# Top_PCB.net
KiCad netlist of a schematic drawn in EAGLE
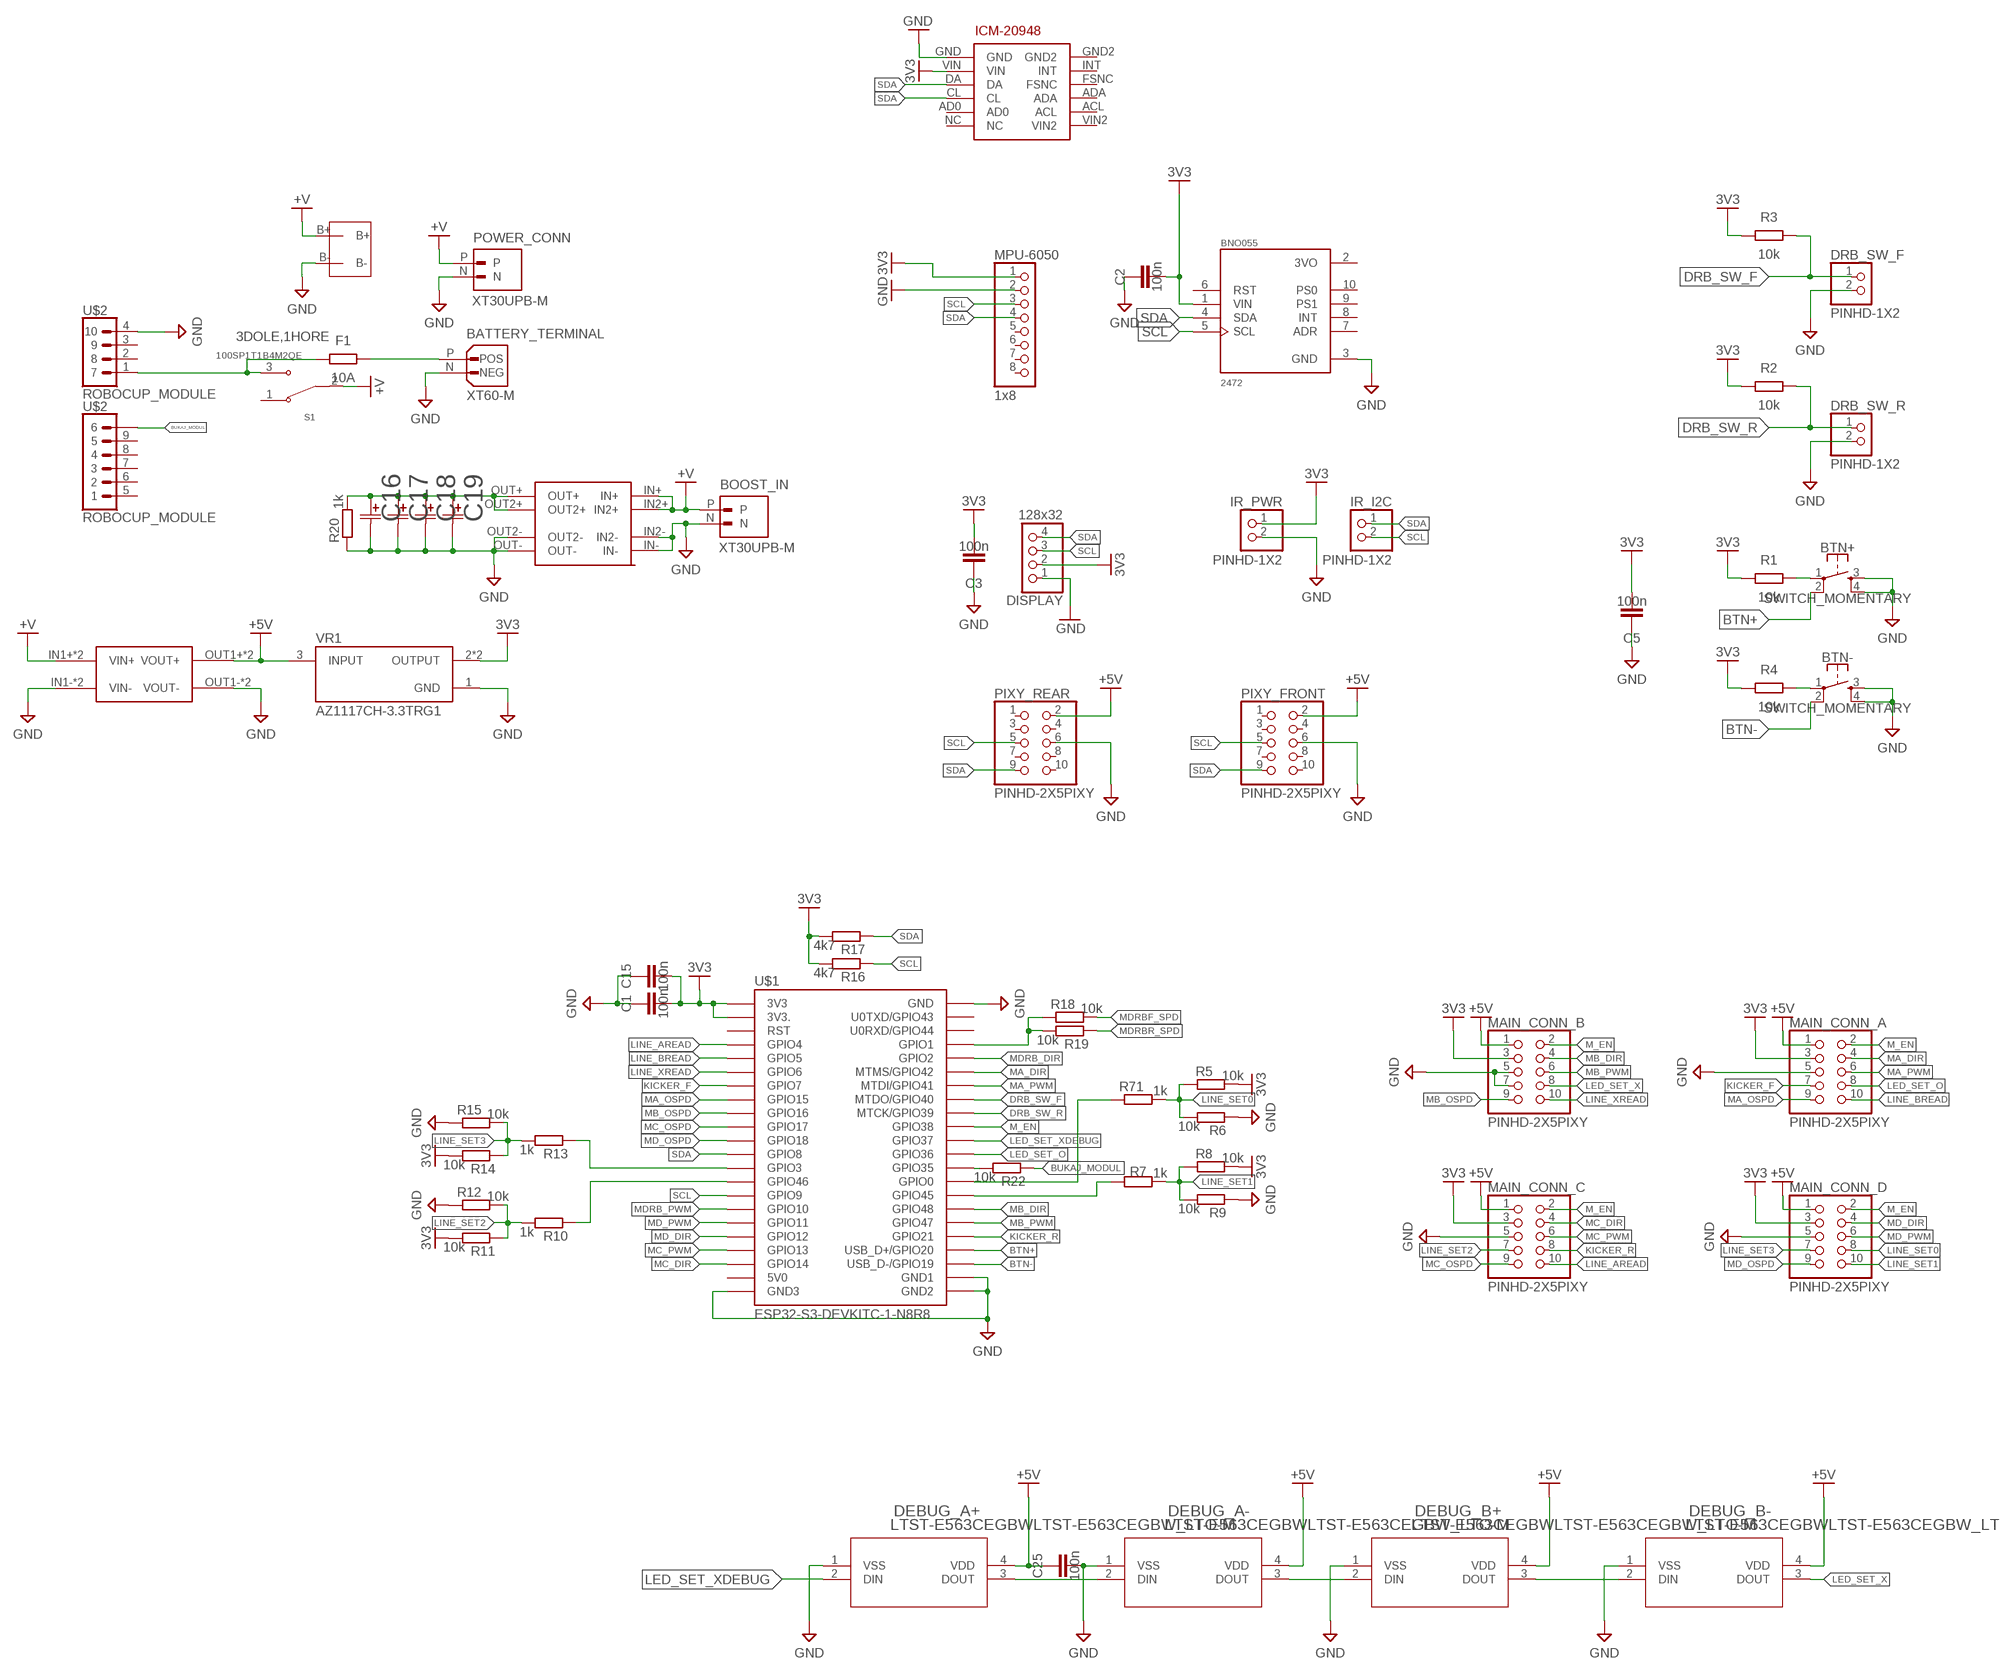
[diagram p0: schematic, sheet 1, part 1 of 2]
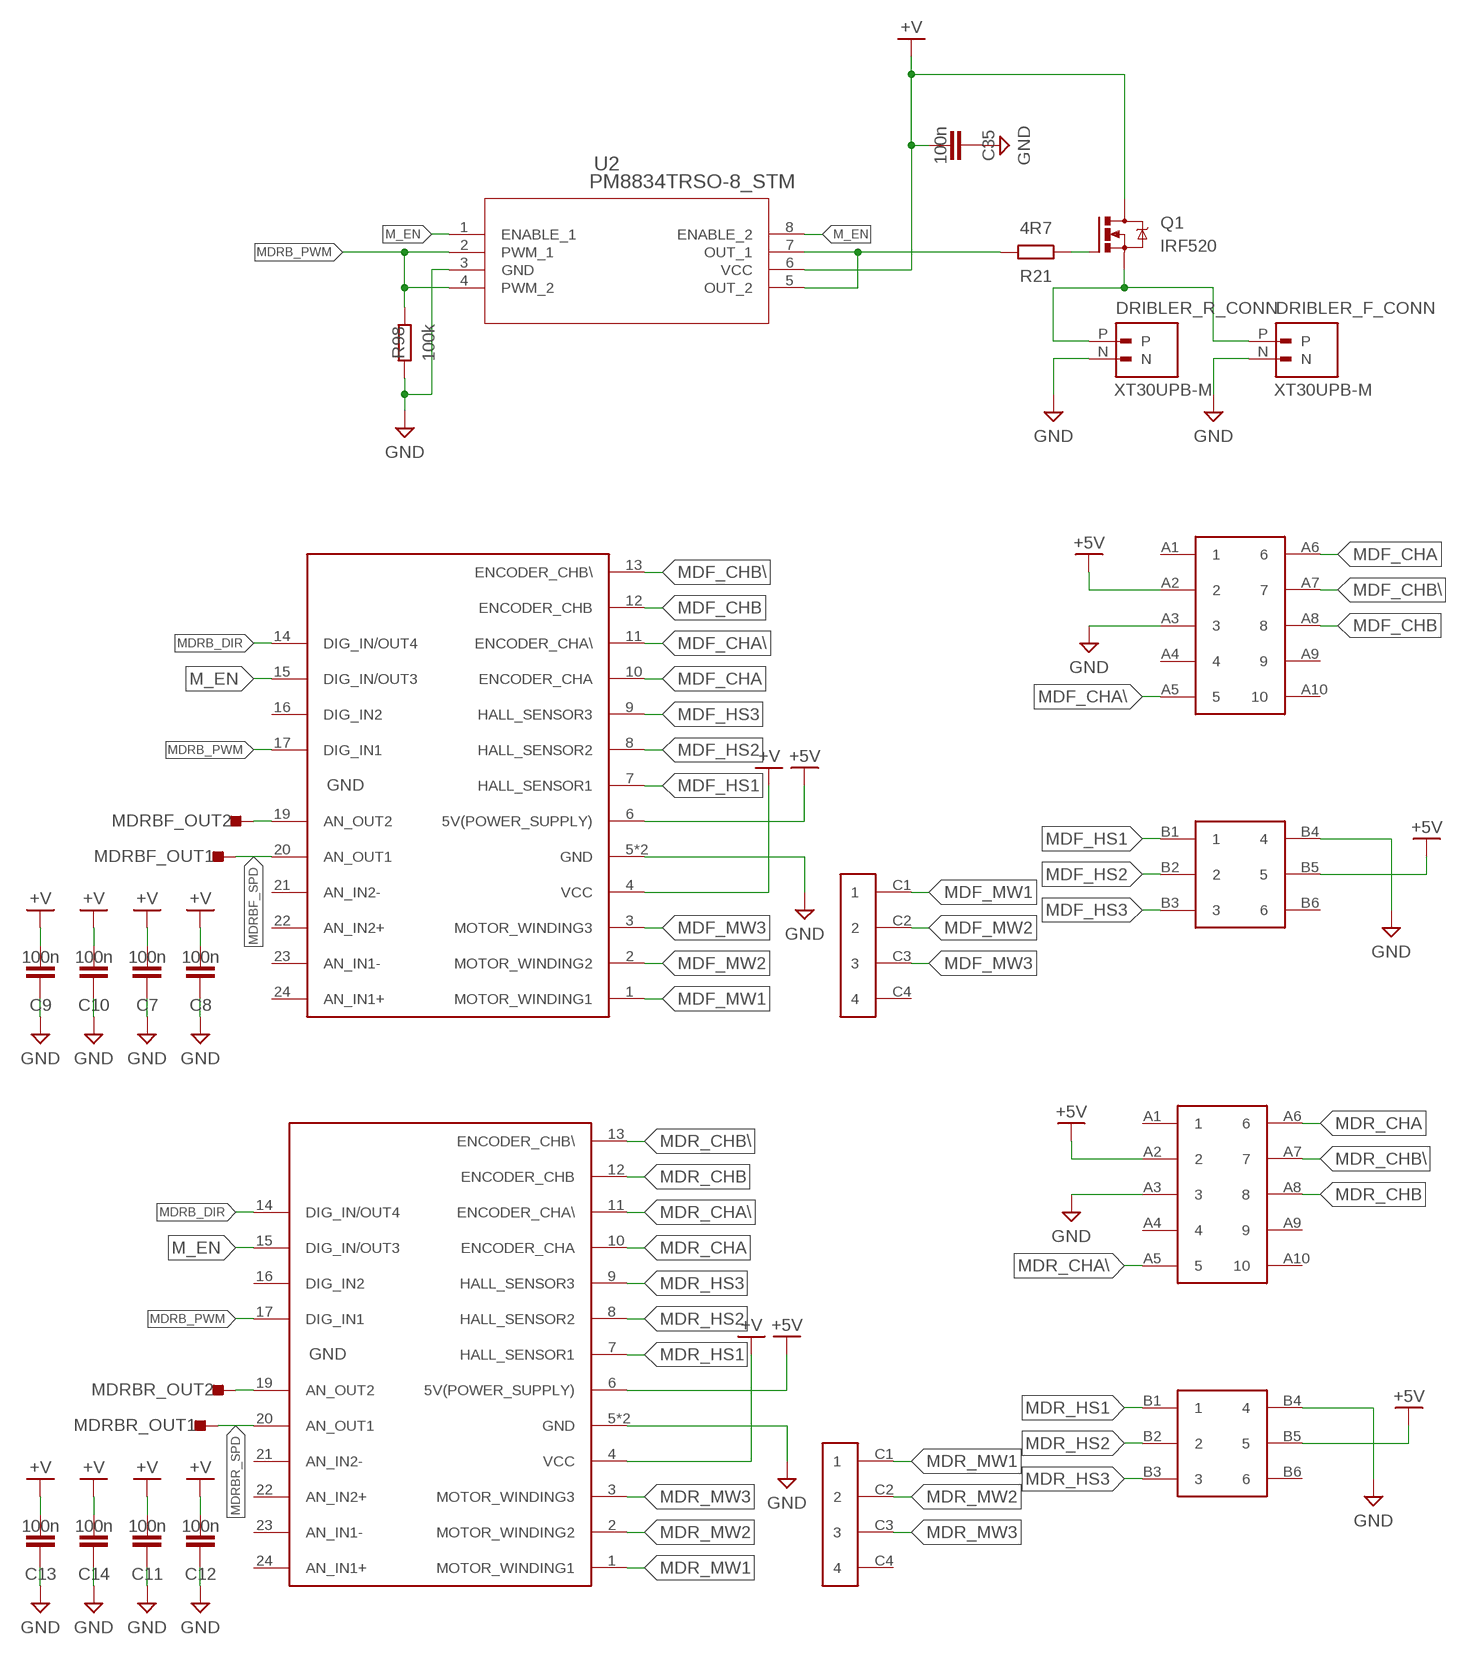
[diagram p1: schematic, sheet 1, part 2 of 2]

(export (version "E")
  (design (tool "Eeschema 10.0.6"))
  (components
    (comp (ref "BATTERY_TERMINAL")
      (value "XT60-M")
      (footprint "eagle-import:AMASS_XT60-M")
      (fields (field (name "MF") "AMASS"))
      (libsource (lib "eagle-import") (part "XT60-M"))
    )
    (comp (ref "BATT_VOLTAGE")
      (value "BATT_V_METER")
      (footprint "eagle-import:1X02")
      (libsource (lib "eagle-import") (part "BATT_V_METER"))
    )
    (comp (ref "BNO055")
      (value "2472")
      (footprint "eagle-import:MODULE_2472")
      (fields (field (name "MF") "Adafruit"))
      (libsource (lib "eagle-import") (part "2472"))
    )
    (comp (ref "BOOST_IN")
      (value "XT30UPB-M")
      (footprint "eagle-import:AMASS_XT30UPB-M")
      (fields (field (name "MF") "amass"))
      (libsource (lib "eagle-import") (part "XT30UPB-M"))
    )
    (comp (ref "BTN+")
      (value "SWITCH_MOMENTARY")
      (footprint "eagle-import:SWITCH-MOMENTARY-PTH-6.5MM")
      (libsource (lib "eagle-import") (part "SWITCH_MOMENTARY"))
    )
    (comp (ref "BTN-")
      (value "SWITCH_MOMENTARY")
      (footprint "eagle-import:SWITCH-MOMENTARY-PTH-6.5MM")
      (libsource (lib "eagle-import") (part "SWITCH_MOMENTARY"))
    )
    (comp (ref "C1")
      (value "100n")
      (footprint "eagle-import:CAPC2012X110")
      (libsource (lib "eagle-import") (part "CCHIP-0805(2012-METRIC)_"))
    )
    (comp (ref "C2")
      (value "100n")
      (footprint "eagle-import:CAPC2012X110")
      (libsource (lib "eagle-import") (part "CCHIP-0805(2012-METRIC)_"))
    )
    (comp (ref "C3")
      (value "100n")
      (footprint "eagle-import:CAPC2012X110")
      (libsource (lib "eagle-import") (part "CCHIP-0805(2012-METRIC)_"))
    )
    (comp (ref "C5")
      (value "100n")
      (footprint "eagle-import:CAPC2012X110")
      (libsource (lib "eagle-import") (part "CCHIP-0805(2012-METRIC)_"))
    )
    (comp (ref "C7")
      (value "100n")
      (footprint "eagle-import:CAPC2012X110")
      (libsource (lib "eagle-import") (part "CCHIP-0805(2012-METRIC)_"))
    )
    (comp (ref "C8")
      (value "100n")
      (footprint "eagle-import:CAPC2012X110")
      (libsource (lib "eagle-import") (part "CCHIP-0805(2012-METRIC)_"))
    )
    (comp (ref "C9")
      (value "100n")
      (footprint "eagle-import:CAPC2012X110")
      (libsource (lib "eagle-import") (part "CCHIP-0805(2012-METRIC)_"))
    )
    (comp (ref "C10")
      (value "100n")
      (footprint "eagle-import:CAPC2012X110")
      (libsource (lib "eagle-import") (part "CCHIP-0805(2012-METRIC)_"))
    )
    (comp (ref "C11")
      (value "100n")
      (footprint "eagle-import:CAPC2012X110")
      (libsource (lib "eagle-import") (part "CCHIP-0805(2012-METRIC)_"))
    )
    (comp (ref "C12")
      (value "100n")
      (footprint "eagle-import:CAPC2012X110")
      (libsource (lib "eagle-import") (part "CCHIP-0805(2012-METRIC)_"))
    )
    (comp (ref "C13")
      (value "100n")
      (footprint "eagle-import:CAPC2012X110")
      (libsource (lib "eagle-import") (part "CCHIP-0805(2012-METRIC)_"))
    )
    (comp (ref "C14")
      (value "100n")
      (footprint "eagle-import:CAPC2012X110")
      (libsource (lib "eagle-import") (part "CCHIP-0805(2012-METRIC)_"))
    )
    (comp (ref "C15")
      (value "100n")
      (footprint "eagle-import:CAPC2012X110")
      (libsource (lib "eagle-import") (part "CCHIP-0805(2012-METRIC)_"))
    )
    (comp (ref "C16")
      (value "1mF")
      (footprint "eagle-import:CAP_108CKE_ILC")
      (fields
        (field (name "MANUFACTURER_PART_NUMBER") "108CKE063M")
        (field (name "COPYRIGHT") "Copyright (C) 2026 Ultra Librarian. All rights reserved.")
      )
      (libsource (lib "eagle-import") (part "108CKE063MCAP_108CKE_ILC"))
    )
    (comp (ref "C17")
      (value "1mF")
      (footprint "eagle-import:CAP_108CKE_ILC")
      (fields
        (field (name "MANUFACTURER_PART_NUMBER") "108CKE063M")
        (field (name "COPYRIGHT") "Copyright (C) 2026 Ultra Librarian. All rights reserved.")
      )
      (libsource (lib "eagle-import") (part "108CKE063MCAP_108CKE_ILC"))
    )
    (comp (ref "C18")
      (value "1mF")
      (footprint "eagle-import:CAP_108CKE_ILC")
      (fields
        (field (name "MANUFACTURER_PART_NUMBER") "108CKE063M")
        (field (name "COPYRIGHT") "Copyright (C) 2026 Ultra Librarian. All rights reserved.")
      )
      (libsource (lib "eagle-import") (part "108CKE063MCAP_108CKE_ILC"))
    )
    (comp (ref "C19")
      (value "1mF")
      (footprint "eagle-import:CAP_108CKE_ILC")
      (fields
        (field (name "MANUFACTURER_PART_NUMBER") "108CKE063M")
        (field (name "COPYRIGHT") "Copyright (C) 2026 Ultra Librarian. All rights reserved.")
      )
      (libsource (lib "eagle-import") (part "108CKE063MCAP_108CKE_ILC"))
    )
    (comp (ref "C25")
      (value "100n")
      (footprint "eagle-import:CAPC2012X110")
      (libsource (lib "eagle-import") (part "CCHIP-0805(2012-METRIC)_"))
    )
    (comp (ref "C35")
      (value "100n")
      (footprint "eagle-import:CAPC2012X110")
      (libsource (lib "eagle-import") (part "CCHIP-0805(2012-METRIC)_"))
    )
    (comp (ref "DEBUG_A+")
      (value "LTST-E563CEGBWLTST-E563CEGBW_LTO-M")
      (footprint "eagle-import:LTST-E563CEGBW_LTO-M")
      (fields
        (field (name "MANUFACTURER_PART_NUMBER") "LTST-E563CEGBW")
        (field (name "COPYRIGHT") "Copyright (C) 2025 Ultra Librarian. All rights reserved.")
      )
      (libsource (lib "eagle-import") (part "LTST-E563CEGBWLTST-E563CEGBW_LTO-M"))
    )
    (comp (ref "DEBUG_A-")
      (value "LTST-E563CEGBWLTST-E563CEGBW_LTO-M")
      (footprint "eagle-import:LTST-E563CEGBW_LTO-M")
      (fields
        (field (name "MANUFACTURER_PART_NUMBER") "LTST-E563CEGBW")
        (field (name "COPYRIGHT") "Copyright (C) 2025 Ultra Librarian. All rights reserved.")
      )
      (libsource (lib "eagle-import") (part "LTST-E563CEGBWLTST-E563CEGBW_LTO-M"))
    )
    (comp (ref "DEBUG_B+")
      (value "LTST-E563CEGBWLTST-E563CEGBW_LTO-M")
      (footprint "eagle-import:LTST-E563CEGBW_LTO-M")
      (fields
        (field (name "MANUFACTURER_PART_NUMBER") "LTST-E563CEGBW")
        (field (name "COPYRIGHT") "Copyright (C) 2025 Ultra Librarian. All rights reserved.")
      )
      (libsource (lib "eagle-import") (part "LTST-E563CEGBWLTST-E563CEGBW_LTO-M"))
    )
    (comp (ref "DEBUG_B-")
      (value "LTST-E563CEGBWLTST-E563CEGBW_LTO-M")
      (footprint "eagle-import:LTST-E563CEGBW_LTO-M")
      (fields
        (field (name "MANUFACTURER_PART_NUMBER") "LTST-E563CEGBW")
        (field (name "COPYRIGHT") "Copyright (C) 2025 Ultra Librarian. All rights reserved.")
      )
      (libsource (lib "eagle-import") (part "LTST-E563CEGBWLTST-E563CEGBW_LTO-M"))
    )
    (comp (ref "DISPLAY")
      (value "128x32")
      (footprint "eagle-import:1X04")
      (libsource (lib "eagle-import") (part "PINHD-1X4"))
    )
    (comp (ref "DRB_SW_F")
      (value "PINHD-1X2")
      (footprint "eagle-import:1X02")
      (fields (field (name "MANUFACTURER") "Generic"))
      (libsource (lib "eagle-import") (part "PINHD-1X2"))
    )
    (comp (ref "DRB_SW_R")
      (value "PINHD-1X2")
      (footprint "eagle-import:1X02")
      (fields (field (name "MANUFACTURER") "Generic"))
      (libsource (lib "eagle-import") (part "PINHD-1X2"))
    )
    (comp (ref "DRIBLER_F_CONN")
      (value "XT30UPB-M")
      (footprint "eagle-import:AMASS_XT30UPB-M")
      (fields (field (name "MF") "amass"))
      (libsource (lib "eagle-import") (part "XT30UPB-M"))
    )
    (comp (ref "DRIBLER_R_CONN")
      (value "XT30UPB-M")
      (footprint "eagle-import:AMASS_XT30UPB-M")
      (fields (field (name "MF") "amass"))
      (libsource (lib "eagle-import") (part "XT30UPB-M"))
    )
    (comp (ref "F1")
      (value "10A")
      (footprint "eagle-import:RESC3216X70")
      (libsource (lib "eagle-import") (part "RCHIP-1206(3216-METRIC)_"))
    )
    (comp (ref "ICM-20948")
      (value "ICM-20948")
      (footprint "eagle-import:ICM-20948")
      (libsource (lib "eagle-import") (part "ICM-20948"))
    )
    (comp (ref "IR_I2C")
      (value "PINHD-1X2")
      (footprint "eagle-import:1X02")
      (fields (field (name "MANUFACTURER") "Generic"))
      (libsource (lib "eagle-import") (part "PINHD-1X2"))
    )
    (comp (ref "IR_PWR")
      (value "PINHD-1X2")
      (footprint "eagle-import:1X02")
      (fields (field (name "MANUFACTURER") "Generic"))
      (libsource (lib "eagle-import") (part "PINHD-1X2"))
    )
    (comp (ref "MAIN_CONN_A")
      (value "PINHD-2X5PIXY")
      (footprint "eagle-import:2X05")
      (libsource (lib "eagle-import") (part "PINHD-2X5PIXY"))
    )
    (comp (ref "MAIN_CONN_B")
      (value "PINHD-2X5PIXY")
      (footprint "eagle-import:2X05")
      (libsource (lib "eagle-import") (part "PINHD-2X5PIXY"))
    )
    (comp (ref "MAIN_CONN_C")
      (value "PINHD-2X5PIXY")
      (footprint "eagle-import:2X05")
      (libsource (lib "eagle-import") (part "PINHD-2X5PIXY"))
    )
    (comp (ref "MAIN_CONN_D")
      (value "PINHD-2X5PIXY")
      (footprint "eagle-import:2X05")
      (libsource (lib "eagle-import") (part "PINHD-2X5PIXY"))
    )
    (comp (ref "MDRBF_OUT1")
      (value "TESTPOINT_TPS-PAD-036")
      (footprint "eagle-import:TESTPOINT_PAD-036")
      (libsource (lib "eagle-import") (part "TESTPOINT_TPS-PAD-036"))
    )
    (comp (ref "MDRBF_OUT2")
      (value "TESTPOINT_TPS-PAD-036")
      (footprint "eagle-import:TESTPOINT_PAD-036")
      (libsource (lib "eagle-import") (part "TESTPOINT_TPS-PAD-036"))
    )
    (comp (ref "MDRBR_OUT1")
      (value "TESTPOINT_TPS-PAD-036")
      (footprint "eagle-import:TESTPOINT_PAD-036")
      (libsource (lib "eagle-import") (part "TESTPOINT_TPS-PAD-036"))
    )
    (comp (ref "MDRBR_OUT2")
      (value "TESTPOINT_TPS-PAD-036")
      (footprint "eagle-import:TESTPOINT_PAD-036")
      (libsource (lib "eagle-import") (part "TESTPOINT_TPS-PAD-036"))
    )
    (comp (ref "MPU-6050")
      (value "1x8")
      (footprint "eagle-import:1X08")
      (libsource (lib "eagle-import") (part "PINHD-1X8"))
    )
    (comp (ref "PIXY_FRONT")
      (value "PINHD-2X5PIXY")
      (footprint "eagle-import:2X05")
      (libsource (lib "eagle-import") (part "PINHD-2X5PIXY"))
    )
    (comp (ref "PIXY_REAR")
      (value "PINHD-2X5PIXY")
      (footprint "eagle-import:2X05")
      (libsource (lib "eagle-import") (part "PINHD-2X5PIXY"))
    )
    (comp (ref "POWER_CONN")
      (value "XT30UPB-M")
      (footprint "eagle-import:AMASS_XT30UPB-M")
      (fields (field (name "MF") "amass"))
      (libsource (lib "eagle-import") (part "XT30UPB-M"))
    )
    (comp (ref "Q1")
      (value "IRF520")
      (footprint "eagle-import:TO220BV")
      (fields (field (name "MANUFACTURER") "Infineon Technologies") (field (name "MPN") "IRF520NPBF"))
      (libsource (lib "eagle-import") (part "NMOSFET__TO220IRF520"))
    )
    (comp (ref "R1")
      (value "10k")
      (footprint "eagle-import:RESC2012X65")
      (libsource (lib "eagle-import") (part "RCHIP-0805(2012-METRIC)_"))
    )
    (comp (ref "R2")
      (value "10k")
      (footprint "eagle-import:RESC2012X65")
      (libsource (lib "eagle-import") (part "RCHIP-0805(2012-METRIC)_"))
    )
    (comp (ref "R3")
      (value "10k")
      (footprint "eagle-import:RESC2012X65")
      (libsource (lib "eagle-import") (part "RCHIP-0805(2012-METRIC)_"))
    )
    (comp (ref "R4")
      (value "10k")
      (footprint "eagle-import:RESC2012X65")
      (libsource (lib "eagle-import") (part "RCHIP-0805(2012-METRIC)_"))
    )
    (comp (ref "R5")
      (value "10k")
      (footprint "eagle-import:RESC2012X65")
      (libsource (lib "eagle-import") (part "RCHIP-0805(2012-METRIC)_"))
    )
    (comp (ref "R6")
      (value "10k")
      (footprint "eagle-import:RESC2012X65")
      (libsource (lib "eagle-import") (part "RCHIP-0805(2012-METRIC)_"))
    )
    (comp (ref "R7")
      (value "1k")
      (footprint "eagle-import:RESC2012X65")
      (libsource (lib "eagle-import") (part "RCHIP-0805(2012-METRIC)_"))
    )
    (comp (ref "R8")
      (value "10k")
      (footprint "eagle-import:RESC2012X65")
      (libsource (lib "eagle-import") (part "RCHIP-0805(2012-METRIC)_"))
    )
    (comp (ref "R9")
      (value "10k")
      (footprint "eagle-import:RESC2012X65")
      (libsource (lib "eagle-import") (part "RCHIP-0805(2012-METRIC)_"))
    )
    (comp (ref "R10")
      (value "1k")
      (footprint "eagle-import:RESC2012X65")
      (libsource (lib "eagle-import") (part "RCHIP-0805(2012-METRIC)_"))
    )
    (comp (ref "R11")
      (value "10k")
      (footprint "eagle-import:RESC2012X65")
      (libsource (lib "eagle-import") (part "RCHIP-0805(2012-METRIC)_"))
    )
    (comp (ref "R12")
      (value "10k")
      (footprint "eagle-import:RESC2012X65")
      (libsource (lib "eagle-import") (part "RCHIP-0805(2012-METRIC)_"))
    )
    (comp (ref "R13")
      (value "1k")
      (footprint "eagle-import:RESC2012X65")
      (libsource (lib "eagle-import") (part "RCHIP-0805(2012-METRIC)_"))
    )
    (comp (ref "R14")
      (value "10k")
      (footprint "eagle-import:RESC2012X65")
      (libsource (lib "eagle-import") (part "RCHIP-0805(2012-METRIC)_"))
    )
    (comp (ref "R15")
      (value "10k")
      (footprint "eagle-import:RESC2012X65")
      (libsource (lib "eagle-import") (part "RCHIP-0805(2012-METRIC)_"))
    )
    (comp (ref "R16")
      (value "4k7")
      (footprint "eagle-import:RESC2012X65")
      (libsource (lib "eagle-import") (part "RCHIP-0805(2012-METRIC)_"))
    )
    (comp (ref "R17")
      (value "4k7")
      (footprint "eagle-import:RESC2012X65")
      (libsource (lib "eagle-import") (part "RCHIP-0805(2012-METRIC)_"))
    )
    (comp (ref "R18")
      (value "10k")
      (footprint "eagle-import:RESC2012X65")
      (libsource (lib "eagle-import") (part "RCHIP-0805(2012-METRIC)_"))
    )
    (comp (ref "R19")
      (value "10k")
      (footprint "eagle-import:RESC2012X65")
      (libsource (lib "eagle-import") (part "RCHIP-0805(2012-METRIC)_"))
    )
    (comp (ref "R20")
      (value "1k")
      (footprint "eagle-import:RESC2012X65")
      (libsource (lib "eagle-import") (part "RCHIP-0805(2012-METRIC)_"))
    )
    (comp (ref "R21")
      (value "4R7")
      (footprint "eagle-import:RESC2012X65")
      (libsource (lib "eagle-import") (part "RCHIP-0805(2012-METRIC)_"))
    )
    (comp (ref "R22")
      (value "10k")
      (footprint "eagle-import:RESC2012X65")
      (libsource (lib "eagle-import") (part "RCHIP-0805(2012-METRIC)_"))
    )
    (comp (ref "R71")
      (value "1k")
      (footprint "eagle-import:RESC2012X65")
      (libsource (lib "eagle-import") (part "RCHIP-0805(2012-METRIC)_"))
    )
    (comp (ref "R98")
      (value "100k")
      (footprint "eagle-import:RESC2012X65")
      (libsource (lib "eagle-import") (part "RCHIP-0805(2012-METRIC)_"))
    )
    (comp (ref "S1")
      (value "100SP1T1B4M2QE")
      (footprint "eagle-import:SW_100SP1T1B4M2QE")
      (fields (field (name "MANUFACTURER") "E-Switch"))
      (libsource (lib "eagle-import") (part "100SP1T1B4M2QE"))
    )
    (comp (ref "U$1")
      (value "ESP32-S3-DEVKITC-1-N8R8")
      (footprint "eagle-import:ESP32-S3-DEVKITC-1-N8R8")
      (fields (field (name "MF") "Espressif Systems") (field (name "SPICEPREFIX") "X"))
      (libsource (lib "eagle-import") (part "ESP32-S3-DEVKITC-1-N8R8"))
    )
    (comp (ref "U$2")
      (value "ROBOCUP_MODULE")
      (footprint "eagle-import:ROBOCUP_MODULE")
      (libsource (lib "eagle-import") (part "ROBOCUP_MODULE"))
    )
    (comp (ref "U$4")
      (value "MP1584")
      (footprint "eagle-import:DC-BRICK")
      (libsource (lib "eagle-import") (part "MP1584"))
    )
    (comp (ref "U$5")
      (value "BOOST")
      (footprint "eagle-import:BOOST")
      (libsource (lib "eagle-import") (part "BOOST"))
    )
    (comp (ref "U$7")
      (value "ESCON24/224/2")
      (footprint "eagle-import:ESCON24_2")
      (libsource (lib "eagle-import") (part "ESCON24/224/2"))
    )
    (comp (ref "U$8")
      (value "PIN2.54-2X5")
      (footprint "eagle-import:PIN2.54-2X5")
      (libsource (lib "eagle-import") (part "PIN2.54-2X5"))
    )
    (comp (ref "U$9")
      (value "ESCON24/224/2")
      (footprint "eagle-import:ESCON24_2")
      (libsource (lib "eagle-import") (part "ESCON24/224/2"))
    )
    (comp (ref "U$10")
      (value "MX-44914-0601")
      (footprint "eagle-import:MX-44914-0601")
      (libsource (lib "eagle-import") (part "MX-44914-0601"))
    )
    (comp (ref "U$11")
      (value "PIN2.54-2X5")
      (footprint "eagle-import:PIN2.54-2X5")
      (libsource (lib "eagle-import") (part "PIN2.54-2X5"))
    )
    (comp (ref "U$12")
      (value "MX-44914-0601")
      (footprint "eagle-import:MX-44914-0601")
      (libsource (lib "eagle-import") (part "MX-44914-0601"))
    )
    (comp (ref "U$13")
      (value "MX5566")
      (footprint "eagle-import:MX5566")
      (libsource (lib "eagle-import") (part "MX5566"))
    )
    (comp (ref "U$14")
      (value "MX5566")
      (footprint "eagle-import:MX5566")
      (libsource (lib "eagle-import") (part "MX5566"))
    )
    (comp (ref "U2")
      (value "PM8834TRSO-8_STM")
      (footprint "eagle-import:SO-8_STM")
      (fields
        (field (name "MANUFACTURER_PART_NUMBER") "PM8834TR")
        (field (name "COPYRIGHT") "Copyright (C) 2025 Ultra Librarian. All rights reserved.")
      )
      (libsource (lib "eagle-import") (part "PM8834TRSO-8_STM"))
    )
    (comp (ref "VR1")
      (value "AZ1117CH-3.3TRG1")
      (footprint "eagle-import:VREG_AZ1117CH-3.3TRG1")
      (fields (field (name "MANUFACTURER") "Diodes Inc.") (field (name "CREATOR") "ASHISH"))
      (libsource (lib "eagle-import") (part "AZ1117CH-3.3TRG1"))
    )
  )
  (nets
    (net (code "1") (name "+5V") (class "Default")
      (node (ref "C25") (pin "1") (pinfunction "1_1") (pintype "passive"))
      (node (ref "DEBUG_A+") (pin "4") (pinfunction "VDD_4") (pintype "power_in"))
      (node (ref "DEBUG_A-") (pin "4") (pinfunction "VDD_4") (pintype "power_in"))
      (node (ref "DEBUG_B+") (pin "4") (pinfunction "VDD_4") (pintype "power_in"))
      (node (ref "DEBUG_B-") (pin "4") (pinfunction "VDD_4") (pintype "power_in"))
      (node (ref "MAIN_CONN_A") (pin "1") (pinfunction "1_1") (pintype "passive"))
      (node (ref "MAIN_CONN_B") (pin "1") (pinfunction "1_1") (pintype "passive"))
      (node (ref "MAIN_CONN_C") (pin "1") (pinfunction "1_1") (pintype "passive"))
      (node (ref "MAIN_CONN_D") (pin "1") (pinfunction "1_1") (pintype "passive"))
      (node (ref "PIXY_FRONT") (pin "2") (pinfunction "2_2") (pintype "passive"))
      (node (ref "PIXY_REAR") (pin "2") (pinfunction "2_2") (pintype "passive"))
      (node (ref "U$10") (pin "B5") (pinfunction "5_B5") (pintype "bidirectional"))
      (node (ref "U$11") (pin "A2") (pinfunction "2_A2") (pintype "bidirectional"))
      (node (ref "U$12") (pin "B5") (pinfunction "5_B5") (pintype "bidirectional"))
      (node (ref "U$4") (pin "OUT1+") (pinfunction "VOUT+_OUT1+") (pintype "output"))
      (node (ref "U$4") (pin "OUT2+") (pinfunction "VOUT+_OUT2+") (pintype "output"))
      (node (ref "U$7") (pin "6") (pinfunction "5V(POWER_SUPPLY)_6") (pintype "bidirectional"))
      (node (ref "U$8") (pin "A2") (pinfunction "2_A2") (pintype "bidirectional"))
      (node (ref "U$9") (pin "6") (pinfunction "5V(POWER_SUPPLY)_6") (pintype "bidirectional"))
      (node (ref "VR1") (pin "3") (pinfunction "INPUT_3") (pintype "input"))
    )
    (net (code "2") (name "+V") (class "Default")
      (node (ref "BATT_VOLTAGE") (pin "B+") (pinfunction "B+_B+") (pintype "bidirectional"))
      (node (ref "BOOST_IN") (pin "P") (pinfunction "P_P") (pintype "passive"))
      (node (ref "C10") (pin "2") (pinfunction "2_2") (pintype "passive"))
      (node (ref "C11") (pin "2") (pinfunction "2_2") (pintype "passive"))
      (node (ref "C12") (pin "2") (pinfunction "2_2") (pintype "passive"))
      (node (ref "C13") (pin "2") (pinfunction "2_2") (pintype "passive"))
      (node (ref "C14") (pin "2") (pinfunction "2_2") (pintype "passive"))
      (node (ref "C35") (pin "2") (pinfunction "2_2") (pintype "passive"))
      (node (ref "C7") (pin "2") (pinfunction "2_2") (pintype "passive"))
      (node (ref "C8") (pin "2") (pinfunction "2_2") (pintype "passive"))
      (node (ref "C9") (pin "2") (pinfunction "2_2") (pintype "passive"))
      (node (ref "POWER_CONN") (pin "P") (pinfunction "P_P") (pintype "passive"))
      (node (ref "Q1") (pin "D") (pinfunction "D_D") (pintype "passive"))
      (node (ref "S1") (pin "2") (pinfunction "2_2") (pintype "passive"))
      (node (ref "U$4") (pin "IN1+") (pinfunction "VIN+_IN1+") (pintype "input"))
      (node (ref "U$4") (pin "IN2+") (pinfunction "VIN+_IN2+") (pintype "input"))
      (node (ref "U$5") (pin "IN+") (pinfunction "IN+_IN+") (pintype "bidirectional"))
      (node (ref "U$5") (pin "IN2+") (pinfunction "IN2+_IN2+") (pintype "bidirectional"))
      (node (ref "U$7") (pin "4") (pinfunction "VCC_4") (pintype "bidirectional"))
      (node (ref "U$9") (pin "4") (pinfunction "VCC_4") (pintype "bidirectional"))
      (node (ref "U2") (pin "6") (pinfunction "VCC_6") (pintype "power_in"))
    )
    (net (code "3") (name "/3DOLE,1HORE") (class "Default")
      (node (ref "F1") (pin "1") (pinfunction "1_1") (pintype "passive"))
      (node (ref "S1") (pin "3") (pinfunction "3_3") (pintype "passive"))
      (node (ref "U$2") (pin "1") (pinfunction "7_1") (pintype "passive"))
    )
    (net (code "4") (name "/3VO") (class "Default")
      (node (ref "BNO055") (pin "2") (pinfunction "3VO_2") (pintype "power_in"))
    )
    (net (code "5") (name "/5V0") (class "Default")
      (node (ref "U$1") (pin "J1_21") (pinfunction "5V0_J1_21") (pintype "power_in"))
    )
    (net (code "6") (name "3V3") (class "Default")
      (node (ref "BNO055") (pin "1") (pinfunction "VIN_1") (pintype "input"))
      (node (ref "C1") (pin "2") (pinfunction "2_2") (pintype "passive"))
      (node (ref "C15") (pin "2") (pinfunction "2_2") (pintype "passive"))
      (node (ref "C2") (pin "2") (pinfunction "2_2") (pintype "passive"))
      (node (ref "C3") (pin "2") (pinfunction "2_2") (pintype "passive"))
      (node (ref "C5") (pin "2") (pinfunction "2_2") (pintype "passive"))
      (node (ref "DISPLAY") (pin "2") (pinfunction "2_2") (pintype "passive"))
      (node (ref "ICM-20948") (pin "VIN") (pinfunction "VIN_VIN") (pintype "bidirectional"))
      (node (ref "IR_PWR") (pin "1") (pinfunction "1_1") (pintype "passive"))
      (node (ref "MAIN_CONN_A") (pin "3") (pinfunction "3_3") (pintype "passive"))
      (node (ref "MAIN_CONN_B") (pin "3") (pinfunction "3_3") (pintype "passive"))
      (node (ref "MAIN_CONN_C") (pin "3") (pinfunction "3_3") (pintype "passive"))
      (node (ref "MAIN_CONN_D") (pin "3") (pinfunction "3_3") (pintype "passive"))
      (node (ref "MPU-6050") (pin "1") (pinfunction "1_1") (pintype "passive"))
      (node (ref "R1") (pin "1") (pinfunction "1_1") (pintype "passive"))
      (node (ref "R11") (pin "1") (pinfunction "1_1") (pintype "passive"))
      (node (ref "R14") (pin "1") (pinfunction "1_1") (pintype "passive"))
      (node (ref "R16") (pin "1") (pinfunction "1_1") (pintype "passive"))
      (node (ref "R17") (pin "1") (pinfunction "1_1") (pintype "passive"))
      (node (ref "R2") (pin "1") (pinfunction "1_1") (pintype "passive"))
      (node (ref "R3") (pin "1") (pinfunction "1_1") (pintype "passive"))
      (node (ref "R4") (pin "1") (pinfunction "1_1") (pintype "passive"))
      (node (ref "R5") (pin "1") (pinfunction "1_1") (pintype "passive"))
      (node (ref "R8") (pin "1") (pinfunction "1_1") (pintype "passive"))
      (node (ref "U$1") (pin "J1_1") (pinfunction "3V3_J1_1") (pintype "power_in"))
      (node (ref "U$1") (pin "J1_2") (pinfunction "3V3._J1_2") (pintype "power_in"))
      (node (ref "VR1") (pin "2") (pinfunction "OUTPUT_2") (pintype "output"))
      (node (ref "VR1") (pin "4") (pinfunction "OUTPUT_4") (pintype "output"))
    )
    (net (code "7") (name "BTN+") (class "Default")
      (node (ref "BTN+") (pin "2") (pinfunction "2_2") (pintype "passive"))
      (node (ref "U$1") (pin "J3_19") (pinfunction "USB_D+/GPIO20_J3_19") (pintype "bidirectional"))
    )
    (net (code "8") (name "BTN-") (class "Default")
      (node (ref "BTN-") (pin "2") (pinfunction "2_2") (pintype "passive"))
      (node (ref "U$1") (pin "J3_20") (pinfunction "USB_D-/GPIO19_J3_20") (pintype "bidirectional"))
    )
    (net (code "9") (name "BUKAJ_MODUL") (class "Default")
      (node (ref "R22") (pin "2") (pinfunction "2_2") (pintype "passive"))
      (node (ref "U$2") (pin "10") (pinfunction "6_10") (pintype "passive"))
    )
    (net (code "10") (name "DRB_SW_F") (class "Default")
      (node (ref "DRB_SW_F") (pin "1") (pinfunction "1_1") (pintype "passive"))
      (node (ref "R3") (pin "2") (pinfunction "2_2") (pintype "passive"))
      (node (ref "U$1") (pin "J3_8") (pinfunction "MTDO/GPIO40_J3_8") (pintype "bidirectional"))
    )
    (net (code "11") (name "DRB_SW_R") (class "Default")
      (node (ref "DRB_SW_R") (pin "1") (pinfunction "1_1") (pintype "passive"))
      (node (ref "R2") (pin "2") (pinfunction "2_2") (pintype "passive"))
      (node (ref "U$1") (pin "J3_9") (pinfunction "MTCK/GPIO39_J3_9") (pintype "bidirectional"))
    )
    (net (code "12") (name "GND") (class "Default")
      (node (ref "BATTERY_TERMINAL") (pin "N") (pinfunction "NEG_N") (pintype "passive"))
      (node (ref "BATT_VOLTAGE") (pin "B-") (pinfunction "B-_B-") (pintype "bidirectional"))
      (node (ref "BNO055") (pin "3") (pinfunction "GND_3") (pintype "power_in"))
      (node (ref "BOOST_IN") (pin "N") (pinfunction "N_N") (pintype "passive"))
      (node (ref "BTN+") (pin "3") (pinfunction "3_3") (pintype "passive"))
      (node (ref "BTN+") (pin "4") (pinfunction "4_4") (pintype "passive"))
      (node (ref "BTN-") (pin "3") (pinfunction "3_3") (pintype "passive"))
      (node (ref "BTN-") (pin "4") (pinfunction "4_4") (pintype "passive"))
      (node (ref "C1") (pin "1") (pinfunction "1_1") (pintype "passive"))
      (node (ref "C10") (pin "1") (pinfunction "1_1") (pintype "passive"))
      (node (ref "C11") (pin "1") (pinfunction "1_1") (pintype "passive"))
      (node (ref "C12") (pin "1") (pinfunction "1_1") (pintype "passive"))
      (node (ref "C13") (pin "1") (pinfunction "1_1") (pintype "passive"))
      (node (ref "C14") (pin "1") (pinfunction "1_1") (pintype "passive"))
      (node (ref "C15") (pin "1") (pinfunction "1_1") (pintype "passive"))
      (node (ref "C16") (pin "2") (pinfunction "2_2") (pintype "passive"))
      (node (ref "C17") (pin "2") (pinfunction "2_2") (pintype "passive"))
      (node (ref "C18") (pin "2") (pinfunction "2_2") (pintype "passive"))
      (node (ref "C19") (pin "2") (pinfunction "2_2") (pintype "passive"))
      (node (ref "C2") (pin "1") (pinfunction "1_1") (pintype "passive"))
      (node (ref "C25") (pin "2") (pinfunction "2_2") (pintype "passive"))
      (node (ref "C3") (pin "1") (pinfunction "1_1") (pintype "passive"))
      (node (ref "C35") (pin "1") (pinfunction "1_1") (pintype "passive"))
      (node (ref "C5") (pin "1") (pinfunction "1_1") (pintype "passive"))
      (node (ref "C7") (pin "1") (pinfunction "1_1") (pintype "passive"))
      (node (ref "C8") (pin "1") (pinfunction "1_1") (pintype "passive"))
      (node (ref "C9") (pin "1") (pinfunction "1_1") (pintype "passive"))
      (node (ref "DEBUG_A+") (pin "1") (pinfunction "VSS_1") (pintype "passive"))
      (node (ref "DEBUG_A-") (pin "1") (pinfunction "VSS_1") (pintype "passive"))
      (node (ref "DEBUG_B+") (pin "1") (pinfunction "VSS_1") (pintype "passive"))
      (node (ref "DEBUG_B-") (pin "1") (pinfunction "VSS_1") (pintype "passive"))
      (node (ref "DISPLAY") (pin "1") (pinfunction "1_1") (pintype "passive"))
      (node (ref "DRB_SW_F") (pin "2") (pinfunction "2_2") (pintype "passive"))
      (node (ref "DRB_SW_R") (pin "2") (pinfunction "2_2") (pintype "passive"))
      (node (ref "DRIBLER_F_CONN") (pin "N") (pinfunction "N_N") (pintype "passive"))
      (node (ref "DRIBLER_R_CONN") (pin "N") (pinfunction "N_N") (pintype "passive"))
      (node (ref "ICM-20948") (pin "GND") (pinfunction "GND_GND") (pintype "bidirectional"))
      (node (ref "IR_PWR") (pin "2") (pinfunction "2_2") (pintype "passive"))
      (node (ref "MAIN_CONN_A") (pin "5") (pinfunction "5_5") (pintype "passive"))
      (node (ref "MAIN_CONN_B") (pin "5") (pinfunction "5_5") (pintype "passive"))
      (node (ref "MAIN_CONN_B") (pin "7") (pinfunction "7_7") (pintype "passive"))
      (node (ref "MAIN_CONN_C") (pin "5") (pinfunction "5_5") (pintype "passive"))
      (node (ref "MAIN_CONN_D") (pin "5") (pinfunction "5_5") (pintype "passive"))
      (node (ref "MPU-6050") (pin "2") (pinfunction "2_2") (pintype "passive"))
      (node (ref "PIXY_FRONT") (pin "6") (pinfunction "6_6") (pintype "passive"))
      (node (ref "PIXY_REAR") (pin "6") (pinfunction "6_6") (pintype "passive"))
      (node (ref "POWER_CONN") (pin "N") (pinfunction "N_N") (pintype "passive"))
      (node (ref "R12") (pin "2") (pinfunction "2_2") (pintype "passive"))
      (node (ref "R15") (pin "2") (pinfunction "2_2") (pintype "passive"))
      (node (ref "R20") (pin "2") (pinfunction "2_2") (pintype "passive"))
      (node (ref "R6") (pin "2") (pinfunction "2_2") (pintype "passive"))
      (node (ref "R9") (pin "2") (pinfunction "2_2") (pintype "passive"))
      (node (ref "R98") (pin "1") (pinfunction "1_1") (pintype "passive"))
      (node (ref "U$1") (pin "J1_22") (pinfunction "GND3_J1_22") (pintype "power_in"))
      (node (ref "U$1") (pin "J3_1") (pinfunction "GND_J3_1") (pintype "power_in"))
      (node (ref "U$1") (pin "J3_21") (pinfunction "GND1_J3_21") (pintype "power_in"))
      (node (ref "U$1") (pin "J3_22") (pinfunction "GND2_J3_22") (pintype "power_in"))
      (node (ref "U$10") (pin "B4") (pinfunction "4_B4") (pintype "bidirectional"))
      (node (ref "U$11") (pin "A3") (pinfunction "3_A3") (pintype "bidirectional"))
      (node (ref "U$12") (pin "B4") (pinfunction "4_B4") (pintype "bidirectional"))
      (node (ref "U$2") (pin "4") (pinfunction "10_4") (pintype "passive"))
      (node (ref "U$4") (pin "IN1-") (pinfunction "VIN-_IN1-") (pintype "input"))
      (node (ref "U$4") (pin "IN2-") (pinfunction "VIN-_IN2-") (pintype "input"))
      (node (ref "U$4") (pin "OUT1-") (pinfunction "VOUT-_OUT1-") (pintype "output"))
      (node (ref "U$4") (pin "OUT2-") (pinfunction "VOUT-_OUT2-") (pintype "output"))
      (node (ref "U$5") (pin "IN-") (pinfunction "IN-_IN-") (pintype "bidirectional"))
      (node (ref "U$5") (pin "IN2-") (pinfunction "IN2-_IN2-") (pintype "bidirectional"))
      (node (ref "U$5") (pin "OUT-") (pinfunction "OUT-_OUT-") (pintype "bidirectional"))
      (node (ref "U$5") (pin "OUT2-") (pinfunction "OUT2-_OUT2-") (pintype "bidirectional"))
      (node (ref "U$7") (pin "18") (pinfunction "GND_18") (pintype "bidirectional"))
      (node (ref "U$7") (pin "5") (pinfunction "GND_5") (pintype "bidirectional"))
      (node (ref "U$8") (pin "A3") (pinfunction "3_A3") (pintype "bidirectional"))
      (node (ref "U$9") (pin "18") (pinfunction "GND_18") (pintype "bidirectional"))
      (node (ref "U$9") (pin "5") (pinfunction "GND_5") (pintype "bidirectional"))
      (node (ref "U2") (pin "3") (pinfunction "GND_3") (pintype "passive"))
      (node (ref "VR1") (pin "1") (pinfunction "GND_1") (pintype "power_in"))
    )
    (net (code "13") (name "KICKER_F") (class "Default")
      (node (ref "MAIN_CONN_A") (pin "7") (pinfunction "7_7") (pintype "passive"))
      (node (ref "U$1") (pin "J1_7") (pinfunction "GPIO7_J1_7") (pintype "bidirectional"))
    )
    (net (code "14") (name "KICKER_R") (class "Default")
      (node (ref "MAIN_CONN_C") (pin "8") (pinfunction "8_8") (pintype "passive"))
      (node (ref "U$1") (pin "J3_18") (pinfunction "GPIO21_J3_18") (pintype "bidirectional"))
    )
    (net (code "15") (name "LED_SET_O") (class "Default")
      (node (ref "MAIN_CONN_A") (pin "8") (pinfunction "8_8") (pintype "passive"))
      (node (ref "U$1") (pin "J3_12") (pinfunction "GPIO36_J3_12") (pintype "bidirectional"))
    )
    (net (code "16") (name "LED_SET_X") (class "Default")
      (node (ref "DEBUG_B-") (pin "3") (pinfunction "DOUT_3") (pintype "output"))
      (node (ref "MAIN_CONN_B") (pin "8") (pinfunction "8_8") (pintype "passive"))
    )
    (net (code "17") (name "LED_SET_XDEBUG") (class "Default")
      (node (ref "DEBUG_A+") (pin "2") (pinfunction "DIN_2") (pintype "input"))
      (node (ref "U$1") (pin "J3_11") (pinfunction "GPIO37_J3_11") (pintype "bidirectional"))
    )
    (net (code "18") (name "LINE_AREAD") (class "Default")
      (node (ref "MAIN_CONN_C") (pin "10") (pinfunction "10_10") (pintype "passive"))
      (node (ref "U$1") (pin "J1_4") (pinfunction "GPIO4_J1_4") (pintype "bidirectional"))
    )
    (net (code "19") (name "LINE_BREAD") (class "Default")
      (node (ref "MAIN_CONN_A") (pin "10") (pinfunction "10_10") (pintype "passive"))
      (node (ref "U$1") (pin "J1_5") (pinfunction "GPIO5_J1_5") (pintype "bidirectional"))
    )
    (net (code "20") (name "LINE_SET0") (class "Default")
      (node (ref "MAIN_CONN_D") (pin "8") (pinfunction "8_8") (pintype "passive"))
      (node (ref "R5") (pin "2") (pinfunction "2_2") (pintype "passive"))
      (node (ref "R6") (pin "1") (pinfunction "1_1") (pintype "passive"))
      (node (ref "R71") (pin "1") (pinfunction "1_1") (pintype "passive"))
    )
    (net (code "21") (name "LINE_SET1") (class "Default")
      (node (ref "MAIN_CONN_D") (pin "10") (pinfunction "10_10") (pintype "passive"))
      (node (ref "R7") (pin "1") (pinfunction "1_1") (pintype "passive"))
      (node (ref "R8") (pin "2") (pinfunction "2_2") (pintype "passive"))
      (node (ref "R9") (pin "1") (pinfunction "1_1") (pintype "passive"))
    )
    (net (code "22") (name "LINE_SET2") (class "Default")
      (node (ref "MAIN_CONN_C") (pin "7") (pinfunction "7_7") (pintype "passive"))
      (node (ref "R10") (pin "1") (pinfunction "1_1") (pintype "passive"))
      (node (ref "R11") (pin "2") (pinfunction "2_2") (pintype "passive"))
      (node (ref "R12") (pin "1") (pinfunction "1_1") (pintype "passive"))
    )
    (net (code "23") (name "LINE_SET3") (class "Default")
      (node (ref "MAIN_CONN_D") (pin "7") (pinfunction "7_7") (pintype "passive"))
      (node (ref "R13") (pin "1") (pinfunction "1_1") (pintype "passive"))
      (node (ref "R14") (pin "2") (pinfunction "2_2") (pintype "passive"))
      (node (ref "R15") (pin "1") (pinfunction "1_1") (pintype "passive"))
    )
    (net (code "24") (name "LINE_XREAD") (class "Default")
      (node (ref "MAIN_CONN_B") (pin "10") (pinfunction "10_10") (pintype "passive"))
      (node (ref "U$1") (pin "J1_6") (pinfunction "GPIO6_J1_6") (pintype "bidirectional"))
    )
    (net (code "25") (name "MA_DIR") (class "Default")
      (node (ref "MAIN_CONN_A") (pin "4") (pinfunction "4_4") (pintype "passive"))
      (node (ref "U$1") (pin "J3_6") (pinfunction "MTMS/GPIO42_J3_6") (pintype "bidirectional"))
    )
    (net (code "26") (name "MA_OSPD") (class "Default")
      (node (ref "MAIN_CONN_A") (pin "9") (pinfunction "9_9") (pintype "passive"))
      (node (ref "U$1") (pin "J1_8") (pinfunction "GPIO15_J1_8") (pintype "bidirectional"))
    )
    (net (code "27") (name "MA_PWM") (class "Default")
      (node (ref "MAIN_CONN_A") (pin "6") (pinfunction "6_6") (pintype "passive"))
      (node (ref "U$1") (pin "J3_7") (pinfunction "MTDI/GPIO41_J3_7") (pintype "bidirectional"))
    )
    (net (code "28") (name "MB_DIR") (class "Default")
      (node (ref "MAIN_CONN_B") (pin "4") (pinfunction "4_4") (pintype "passive"))
      (node (ref "U$1") (pin "J3_16") (pinfunction "GPIO48_J3_16") (pintype "bidirectional"))
    )
    (net (code "29") (name "MB_OSPD") (class "Default")
      (node (ref "MAIN_CONN_B") (pin "9") (pinfunction "9_9") (pintype "passive"))
      (node (ref "U$1") (pin "J1_9") (pinfunction "GPIO16_J1_9") (pintype "bidirectional"))
    )
    (net (code "30") (name "MB_PWM") (class "Default")
      (node (ref "MAIN_CONN_B") (pin "6") (pinfunction "6_6") (pintype "passive"))
      (node (ref "U$1") (pin "J3_17") (pinfunction "GPIO47_J3_17") (pintype "bidirectional"))
    )
    (net (code "31") (name "MC_DIR") (class "Default")
      (node (ref "MAIN_CONN_C") (pin "4") (pinfunction "4_4") (pintype "passive"))
      (node (ref "U$1") (pin "J1_20") (pinfunction "GPIO14_J1_20") (pintype "bidirectional"))
    )
    (net (code "32") (name "MC_OSPD") (class "Default")
      (node (ref "MAIN_CONN_C") (pin "9") (pinfunction "9_9") (pintype "passive"))
      (node (ref "U$1") (pin "J1_10") (pinfunction "GPIO17_J1_10") (pintype "bidirectional"))
    )
    (net (code "33") (name "MC_PWM") (class "Default")
      (node (ref "MAIN_CONN_C") (pin "6") (pinfunction "6_6") (pintype "passive"))
      (node (ref "U$1") (pin "J1_19") (pinfunction "GPIO13_J1_19") (pintype "bidirectional"))
    )
    (net (code "34") (name "MDF_CHA") (class "Default")
      (node (ref "U$11") (pin "A6") (pinfunction "6_A6") (pintype "bidirectional"))
      (node (ref "U$9") (pin "10") (pinfunction "ENCODER_CHA_10") (pintype "bidirectional"))
    )
    (net (code "35") (name "MDF_CHA\\\\") (class "Default")
      (node (ref "U$11") (pin "A5") (pinfunction "5_A5") (pintype "bidirectional"))
      (node (ref "U$9") (pin "11") (pinfunction "ENCODER_CHA\\\\_11") (pintype "bidirectional"))
    )
    (net (code "36") (name "MDF_CHB") (class "Default")
      (node (ref "U$11") (pin "A8") (pinfunction "8_A8") (pintype "bidirectional"))
      (node (ref "U$9") (pin "12") (pinfunction "ENCODER_CHB_12") (pintype "bidirectional"))
    )
    (net (code "37") (name "MDF_CHB\\\\") (class "Default")
      (node (ref "U$11") (pin "A7") (pinfunction "7_A7") (pintype "bidirectional"))
      (node (ref "U$9") (pin "13") (pinfunction "ENCODER_CHB\\\\_13") (pintype "bidirectional"))
    )
    (net (code "38") (name "MDF_HS1") (class "Default")
      (node (ref "U$12") (pin "B1") (pinfunction "1_B1") (pintype "bidirectional"))
      (node (ref "U$9") (pin "7") (pinfunction "HALL_SENSOR1_7") (pintype "bidirectional"))
    )
    (net (code "39") (name "MDF_HS2") (class "Default")
      (node (ref "U$12") (pin "B2") (pinfunction "2_B2") (pintype "bidirectional"))
      (node (ref "U$9") (pin "8") (pinfunction "HALL_SENSOR2_8") (pintype "bidirectional"))
    )
    (net (code "40") (name "MDF_HS3") (class "Default")
      (node (ref "U$12") (pin "B3") (pinfunction "3_B3") (pintype "bidirectional"))
      (node (ref "U$9") (pin "9") (pinfunction "HALL_SENSOR3_9") (pintype "bidirectional"))
    )
    (net (code "41") (name "MDF_MW1") (class "Default")
      (node (ref "U$13") (pin "C1") (pinfunction "1_C1") (pintype "bidirectional"))
      (node (ref "U$9") (pin "1") (pinfunction "MOTOR_WINDING1_1") (pintype "bidirectional"))
    )
    (net (code "42") (name "MDF_MW2") (class "Default")
      (node (ref "U$13") (pin "C2") (pinfunction "2_C2") (pintype "bidirectional"))
      (node (ref "U$9") (pin "2") (pinfunction "MOTOR_WINDING2_2") (pintype "bidirectional"))
    )
    (net (code "43") (name "MDF_MW3") (class "Default")
      (node (ref "U$13") (pin "C3") (pinfunction "3_C3") (pintype "bidirectional"))
      (node (ref "U$9") (pin "3") (pinfunction "MOTOR_WINDING3_3") (pintype "bidirectional"))
    )
    (net (code "44") (name "MDRBF_SPD") (class "Default")
      (node (ref "MDRBF_OUT1") (pin "1") (pinfunction "TP_1") (pintype "passive"))
      (node (ref "R18") (pin "1") (pinfunction "1_1") (pintype "passive"))
      (node (ref "U$9") (pin "20") (pinfunction "AN_OUT1_20") (pintype "bidirectional"))
    )
    (net (code "45") (name "MDRBR_SPD") (class "Default")
      (node (ref "MDRBR_OUT1") (pin "1") (pinfunction "TP_1") (pintype "passive"))
      (node (ref "R19") (pin "2") (pinfunction "2_2") (pintype "passive"))
      (node (ref "U$7") (pin "20") (pinfunction "AN_OUT1_20") (pintype "bidirectional"))
    )
    (net (code "46") (name "MDRB_DIR") (class "Default")
      (node (ref "U$1") (pin "J3_5") (pinfunction "GPIO2_J3_5") (pintype "bidirectional"))
      (node (ref "U$7") (pin "14") (pinfunction "DIG_IN/OUT4_14") (pintype "bidirectional"))
      (node (ref "U$9") (pin "14") (pinfunction "DIG_IN/OUT4_14") (pintype "bidirectional"))
    )
    (net (code "47") (name "MDRB_PWM") (class "Default")
      (node (ref "R98") (pin "2") (pinfunction "2_2") (pintype "passive"))
      (node (ref "U$1") (pin "J1_16") (pinfunction "GPIO10_J1_16") (pintype "bidirectional"))
      (node (ref "U$7") (pin "17") (pinfunction "DIG_IN1_17") (pintype "bidirectional"))
      (node (ref "U$9") (pin "17") (pinfunction "DIG_IN1_17") (pintype "bidirectional"))
      (node (ref "U2") (pin "2") (pinfunction "PWM_1_2") (pintype "input"))
      (node (ref "U2") (pin "4") (pinfunction "PWM_2_4") (pintype "input"))
    )
    (net (code "48") (name "MDR_CHA") (class "Default")
      (node (ref "U$7") (pin "10") (pinfunction "ENCODER_CHA_10") (pintype "bidirectional"))
      (node (ref "U$8") (pin "A6") (pinfunction "6_A6") (pintype "bidirectional"))
    )
    (net (code "49") (name "MDR_CHA\\\\") (class "Default")
      (node (ref "U$7") (pin "11") (pinfunction "ENCODER_CHA\\\\_11") (pintype "bidirectional"))
      (node (ref "U$8") (pin "A5") (pinfunction "5_A5") (pintype "bidirectional"))
    )
    (net (code "50") (name "MDR_CHB") (class "Default")
      (node (ref "U$7") (pin "12") (pinfunction "ENCODER_CHB_12") (pintype "bidirectional"))
      (node (ref "U$8") (pin "A8") (pinfunction "8_A8") (pintype "bidirectional"))
    )
    (net (code "51") (name "MDR_CHB\\\\") (class "Default")
      (node (ref "U$7") (pin "13") (pinfunction "ENCODER_CHB\\\\_13") (pintype "bidirectional"))
      (node (ref "U$8") (pin "A7") (pinfunction "7_A7") (pintype "bidirectional"))
    )
    (net (code "52") (name "MDR_HS1") (class "Default")
      (node (ref "U$10") (pin "B1") (pinfunction "1_B1") (pintype "bidirectional"))
      (node (ref "U$7") (pin "7") (pinfunction "HALL_SENSOR1_7") (pintype "bidirectional"))
    )
    (net (code "53") (name "MDR_HS2") (class "Default")
      (node (ref "U$10") (pin "B2") (pinfunction "2_B2") (pintype "bidirectional"))
      (node (ref "U$7") (pin "8") (pinfunction "HALL_SENSOR2_8") (pintype "bidirectional"))
    )
    (net (code "54") (name "MDR_HS3") (class "Default")
      (node (ref "U$10") (pin "B3") (pinfunction "3_B3") (pintype "bidirectional"))
      (node (ref "U$7") (pin "9") (pinfunction "HALL_SENSOR3_9") (pintype "bidirectional"))
    )
    (net (code "55") (name "MDR_MW1") (class "Default")
      (node (ref "U$14") (pin "C1") (pinfunction "1_C1") (pintype "bidirectional"))
      (node (ref "U$7") (pin "1") (pinfunction "MOTOR_WINDING1_1") (pintype "bidirectional"))
    )
    (net (code "56") (name "MDR_MW2") (class "Default")
      (node (ref "U$14") (pin "C2") (pinfunction "2_C2") (pintype "bidirectional"))
      (node (ref "U$7") (pin "2") (pinfunction "MOTOR_WINDING2_2") (pintype "bidirectional"))
    )
    (net (code "57") (name "MDR_MW3") (class "Default")
      (node (ref "U$14") (pin "C3") (pinfunction "3_C3") (pintype "bidirectional"))
      (node (ref "U$7") (pin "3") (pinfunction "MOTOR_WINDING3_3") (pintype "bidirectional"))
    )
    (net (code "58") (name "MD_DIR") (class "Default")
      (node (ref "MAIN_CONN_D") (pin "4") (pinfunction "4_4") (pintype "passive"))
      (node (ref "U$1") (pin "J1_18") (pinfunction "GPIO12_J1_18") (pintype "bidirectional"))
    )
    (net (code "59") (name "MD_OSPD") (class "Default")
      (node (ref "MAIN_CONN_D") (pin "9") (pinfunction "9_9") (pintype "passive"))
      (node (ref "U$1") (pin "J1_11") (pinfunction "GPIO18_J1_11") (pintype "bidirectional"))
    )
    (net (code "60") (name "MD_PWM") (class "Default")
      (node (ref "MAIN_CONN_D") (pin "6") (pinfunction "6_6") (pintype "passive"))
      (node (ref "U$1") (pin "J1_17") (pinfunction "GPIO11_J1_17") (pintype "bidirectional"))
    )
    (net (code "61") (name "M_EN") (class "Default")
      (node (ref "MAIN_CONN_A") (pin "2") (pinfunction "2_2") (pintype "passive"))
      (node (ref "MAIN_CONN_B") (pin "2") (pinfunction "2_2") (pintype "passive"))
      (node (ref "MAIN_CONN_C") (pin "2") (pinfunction "2_2") (pintype "passive"))
      (node (ref "MAIN_CONN_D") (pin "2") (pinfunction "2_2") (pintype "passive"))
      (node (ref "U$1") (pin "J3_10") (pinfunction "GPIO38_J3_10") (pintype "bidirectional"))
      (node (ref "U$7") (pin "15") (pinfunction "DIG_IN/OUT3_15") (pintype "bidirectional"))
      (node (ref "U$9") (pin "15") (pinfunction "DIG_IN/OUT3_15") (pintype "bidirectional"))
      (node (ref "U2") (pin "1") (pinfunction "ENABLE_1_1") (pintype "input"))
      (node (ref "U2") (pin "8") (pinfunction "ENABLE_2_8") (pintype "input"))
    )
    (net (code "62") (name "Net-(BATTERY_TERMINAL-POS)") (class "Default")
      (node (ref "BATTERY_TERMINAL") (pin "P") (pinfunction "POS_P") (pintype "passive"))
      (node (ref "F1") (pin "2") (pinfunction "2_2") (pintype "passive"))
    )
    (net (code "63") (name "Net-(BTN+-Pad1)") (class "Default")
      (node (ref "BTN+") (pin "1") (pinfunction "1_1") (pintype "passive"))
      (node (ref "R1") (pin "2") (pinfunction "2_2") (pintype "passive"))
    )
    (net (code "64") (name "Net-(BTN--Pad1)") (class "Default")
      (node (ref "BTN-") (pin "1") (pinfunction "1_1") (pintype "passive"))
      (node (ref "R4") (pin "2") (pinfunction "2_2") (pintype "passive"))
    )
    (net (code "65") (name "Net-(C16-Pad1)") (class "Default")
      (node (ref "C16") (pin "1") (pinfunction "1_1") (pintype "passive"))
      (node (ref "C17") (pin "1") (pinfunction "1_1") (pintype "passive"))
      (node (ref "C18") (pin "1") (pinfunction "1_1") (pintype "passive"))
      (node (ref "C19") (pin "1") (pinfunction "1_1") (pintype "passive"))
      (node (ref "R20") (pin "1") (pinfunction "1_1") (pintype "passive"))
      (node (ref "U$5") (pin "OUT+") (pinfunction "OUT+_OUT+") (pintype "bidirectional"))
      (node (ref "U$5") (pin "OUT2+") (pinfunction "OUT2+_OUT2+") (pintype "bidirectional"))
    )
    (net (code "66") (name "Net-(DEBUG_A+-DOUT)") (class "Default")
      (node (ref "DEBUG_A+") (pin "3") (pinfunction "DOUT_3") (pintype "output"))
      (node (ref "DEBUG_A-") (pin "2") (pinfunction "DIN_2") (pintype "input"))
    )
    (net (code "67") (name "Net-(DEBUG_A--DOUT)") (class "Default")
      (node (ref "DEBUG_A-") (pin "3") (pinfunction "DOUT_3") (pintype "output"))
      (node (ref "DEBUG_B+") (pin "2") (pinfunction "DIN_2") (pintype "input"))
    )
    (net (code "68") (name "Net-(DEBUG_B+-DOUT)") (class "Default")
      (node (ref "DEBUG_B+") (pin "3") (pinfunction "DOUT_3") (pintype "output"))
      (node (ref "DEBUG_B-") (pin "2") (pinfunction "DIN_2") (pintype "input"))
    )
    (net (code "69") (name "Net-(DRIBLER_F_CONN-PadP)") (class "Default")
      (node (ref "DRIBLER_F_CONN") (pin "P") (pinfunction "P_P") (pintype "passive"))
      (node (ref "DRIBLER_R_CONN") (pin "P") (pinfunction "P_P") (pintype "passive"))
      (node (ref "Q1") (pin "S") (pinfunction "S_S") (pintype "passive"))
    )
    (net (code "70") (name "Net-(MDRBF_OUT2-TP)") (class "Default")
      (node (ref "MDRBF_OUT2") (pin "1") (pinfunction "TP_1") (pintype "passive"))
      (node (ref "U$9") (pin "19") (pinfunction "AN_OUT2_19") (pintype "bidirectional"))
    )
    (net (code "71") (name "Net-(MDRBR_OUT2-TP)") (class "Default")
      (node (ref "MDRBR_OUT2") (pin "1") (pinfunction "TP_1") (pintype "passive"))
      (node (ref "U$7") (pin "19") (pinfunction "AN_OUT2_19") (pintype "bidirectional"))
    )
    (net (code "72") (name "Net-(Q1-PadG)") (class "Default")
      (node (ref "Q1") (pin "G") (pinfunction "G_G") (pintype "passive"))
      (node (ref "R21") (pin "1") (pinfunction "1_1") (pintype "passive"))
    )
    (net (code "73") (name "Net-(U$1-GPIO0)") (class "Default")
      (node (ref "R71") (pin "2") (pinfunction "2_2") (pintype "passive"))
      (node (ref "U$1") (pin "J3_14") (pinfunction "GPIO0_J3_14") (pintype "bidirectional"))
    )
    (net (code "74") (name "Net-(U$1-GPIO1)") (class "Default")
      (node (ref "R18") (pin "2") (pinfunction "2_2") (pintype "passive"))
      (node (ref "R19") (pin "1") (pinfunction "1_1") (pintype "passive"))
      (node (ref "U$1") (pin "J3_4") (pinfunction "GPIO1_J3_4") (pintype "bidirectional"))
    )
    (net (code "75") (name "Net-(U$1-GPIO3)") (class "Default")
      (node (ref "R13") (pin "2") (pinfunction "2_2") (pintype "passive"))
      (node (ref "U$1") (pin "J1_13") (pinfunction "GPIO3_J1_13") (pintype "bidirectional"))
    )
    (net (code "76") (name "Net-(U$1-GPIO35)") (class "Default")
      (node (ref "R22") (pin "1") (pinfunction "1_1") (pintype "passive"))
      (node (ref "U$1") (pin "J3_13") (pinfunction "GPIO35_J3_13") (pintype "bidirectional"))
    )
    (net (code "77") (name "Net-(U$1-GPIO45)") (class "Default")
      (node (ref "R7") (pin "2") (pinfunction "2_2") (pintype "passive"))
      (node (ref "U$1") (pin "J3_15") (pinfunction "GPIO45_J3_15") (pintype "bidirectional"))
    )
    (net (code "78") (name "Net-(U$1-GPIO46)") (class "Default")
      (node (ref "R10") (pin "2") (pinfunction "2_2") (pintype "passive"))
      (node (ref "U$1") (pin "J1_14") (pinfunction "GPIO46_J1_14") (pintype "bidirectional"))
    )
    (net (code "79") (name "Net-(U2-OUT_1)") (class "Default")
      (node (ref "R21") (pin "2") (pinfunction "2_2") (pintype "passive"))
      (node (ref "U2") (pin "5") (pinfunction "OUT_2_5") (pintype "output"))
      (node (ref "U2") (pin "7") (pinfunction "OUT_1_7") (pintype "output"))
    )
    (net (code "80") (name "SCL") (class "Default")
      (node (ref "BNO055") (pin "5") (pinfunction "SCL_5") (pintype "input"))
      (node (ref "DISPLAY") (pin "3") (pinfunction "3_3") (pintype "passive"))
      (node (ref "IR_I2C") (pin "2") (pinfunction "2_2") (pintype "passive"))
      (node (ref "MPU-6050") (pin "3") (pinfunction "3_3") (pintype "passive"))
      (node (ref "PIXY_FRONT") (pin "5") (pinfunction "5_5") (pintype "passive"))
      (node (ref "PIXY_REAR") (pin "5") (pinfunction "5_5") (pintype "passive"))
      (node (ref "R16") (pin "2") (pinfunction "2_2") (pintype "passive"))
      (node (ref "U$1") (pin "J1_15") (pinfunction "GPIO9_J1_15") (pintype "bidirectional"))
    )
    (net (code "81") (name "SDA") (class "Default")
      (node (ref "BNO055") (pin "4") (pinfunction "SDA_4") (pintype "bidirectional"))
      (node (ref "DISPLAY") (pin "4") (pinfunction "4_4") (pintype "passive"))
      (node (ref "ICM-20948") (pin "CL") (pinfunction "CL_CL") (pintype "bidirectional"))
      (node (ref "ICM-20948") (pin "DA") (pinfunction "DA_DA") (pintype "bidirectional"))
      (node (ref "IR_I2C") (pin "1") (pinfunction "1_1") (pintype "passive"))
      (node (ref "MPU-6050") (pin "4") (pinfunction "4_4") (pintype "passive"))
      (node (ref "PIXY_FRONT") (pin "9") (pinfunction "9_9") (pintype "passive"))
      (node (ref "PIXY_REAR") (pin "9") (pinfunction "9_9") (pintype "passive"))
      (node (ref "R17") (pin "2") (pinfunction "2_2") (pintype "passive"))
      (node (ref "U$1") (pin "J1_12") (pinfunction "GPIO8_J1_12") (pintype "bidirectional"))
    )
    (net (code "82") (name "unconnected-(BNO055-ADR-Pad7)") (class "Default")
      (node (ref "BNO055") (pin "7") (pinfunction "ADR_7") (pintype "passive"))
    )
    (net (code "83") (name "unconnected-(BNO055-INT-Pad8)") (class "Default")
      (node (ref "BNO055") (pin "8") (pinfunction "INT_8") (pintype "output"))
    )
    (net (code "84") (name "unconnected-(BNO055-PS0-Pad10)") (class "Default")
      (node (ref "BNO055") (pin "10") (pinfunction "PS0_10") (pintype "bidirectional"))
    )
    (net (code "85") (name "unconnected-(BNO055-PS1-Pad9)") (class "Default")
      (node (ref "BNO055") (pin "9") (pinfunction "PS1_9") (pintype "bidirectional"))
    )
    (net (code "86") (name "unconnected-(BNO055-RST-Pad6)") (class "Default")
      (node (ref "BNO055") (pin "6") (pinfunction "RST_6") (pintype "input"))
    )
    (net (code "87") (name "unconnected-(ICM-20948-PadACL)") (class "Default")
      (node (ref "ICM-20948") (pin "ACL") (pinfunction "ACL_ACL") (pintype "bidirectional"))
    )
    (net (code "88") (name "unconnected-(ICM-20948-PadAD0)") (class "Default")
      (node (ref "ICM-20948") (pin "AD0") (pinfunction "AD0_AD0") (pintype "bidirectional"))
    )
    (net (code "89") (name "unconnected-(ICM-20948-PadADA)") (class "Default")
      (node (ref "ICM-20948") (pin "ADA") (pinfunction "ADA_ADA") (pintype "bidirectional"))
    )
    (net (code "90") (name "unconnected-(ICM-20948-PadFSNC)") (class "Default")
      (node (ref "ICM-20948") (pin "FSNC") (pinfunction "FSNC_FSNC") (pintype "bidirectional"))
    )
    (net (code "91") (name "unconnected-(ICM-20948-PadGND2)") (class "Default")
      (node (ref "ICM-20948") (pin "GND2") (pinfunction "GND2_GND2") (pintype "bidirectional"))
    )
    (net (code "92") (name "unconnected-(ICM-20948-PadINT)") (class "Default")
      (node (ref "ICM-20948") (pin "INT") (pinfunction "INT_INT") (pintype "bidirectional"))
    )
    (net (code "93") (name "unconnected-(ICM-20948-PadNC)") (class "Default")
      (node (ref "ICM-20948") (pin "NC") (pinfunction "NC_NC") (pintype "bidirectional"))
    )
    (net (code "94") (name "unconnected-(ICM-20948-PadVIN2)") (class "Default")
      (node (ref "ICM-20948") (pin "VIN2") (pinfunction "VIN2_VIN2") (pintype "bidirectional"))
    )
    (net (code "95") (name "unconnected-(MPU-6050-Pad5)") (class "Default")
      (node (ref "MPU-6050") (pin "5") (pinfunction "5_5") (pintype "passive"))
    )
    (net (code "96") (name "unconnected-(MPU-6050-Pad6)") (class "Default")
      (node (ref "MPU-6050") (pin "6") (pinfunction "6_6") (pintype "passive"))
    )
    (net (code "97") (name "unconnected-(MPU-6050-Pad7)") (class "Default")
      (node (ref "MPU-6050") (pin "7") (pinfunction "7_7") (pintype "passive"))
    )
    (net (code "98") (name "unconnected-(MPU-6050-Pad8)") (class "Default")
      (node (ref "MPU-6050") (pin "8") (pinfunction "8_8") (pintype "passive"))
    )
    (net (code "99") (name "unconnected-(PIXY_FRONT-Pad1)") (class "Default")
      (node (ref "PIXY_FRONT") (pin "1") (pinfunction "1_1") (pintype "passive"))
    )
    (net (code "100") (name "unconnected-(PIXY_FRONT-Pad3)") (class "Default")
      (node (ref "PIXY_FRONT") (pin "3") (pinfunction "3_3") (pintype "passive"))
    )
    (net (code "101") (name "unconnected-(PIXY_FRONT-Pad4)") (class "Default")
      (node (ref "PIXY_FRONT") (pin "4") (pinfunction "4_4") (pintype "passive"))
    )
    (net (code "102") (name "unconnected-(PIXY_FRONT-Pad7)") (class "Default")
      (node (ref "PIXY_FRONT") (pin "7") (pinfunction "7_7") (pintype "passive"))
    )
    (net (code "103") (name "unconnected-(PIXY_FRONT-Pad8)") (class "Default")
      (node (ref "PIXY_FRONT") (pin "8") (pinfunction "8_8") (pintype "passive"))
    )
    (net (code "104") (name "unconnected-(PIXY_FRONT-Pad10)") (class "Default")
      (node (ref "PIXY_FRONT") (pin "10") (pinfunction "10_10") (pintype "passive"))
    )
    (net (code "105") (name "unconnected-(PIXY_REAR-Pad1)") (class "Default")
      (node (ref "PIXY_REAR") (pin "1") (pinfunction "1_1") (pintype "passive"))
    )
    (net (code "106") (name "unconnected-(PIXY_REAR-Pad3)") (class "Default")
      (node (ref "PIXY_REAR") (pin "3") (pinfunction "3_3") (pintype "passive"))
    )
    (net (code "107") (name "unconnected-(PIXY_REAR-Pad4)") (class "Default")
      (node (ref "PIXY_REAR") (pin "4") (pinfunction "4_4") (pintype "passive"))
    )
    (net (code "108") (name "unconnected-(PIXY_REAR-Pad7)") (class "Default")
      (node (ref "PIXY_REAR") (pin "7") (pinfunction "7_7") (pintype "passive"))
    )
    (net (code "109") (name "unconnected-(PIXY_REAR-Pad8)") (class "Default")
      (node (ref "PIXY_REAR") (pin "8") (pinfunction "8_8") (pintype "passive"))
    )
    (net (code "110") (name "unconnected-(PIXY_REAR-Pad10)") (class "Default")
      (node (ref "PIXY_REAR") (pin "10") (pinfunction "10_10") (pintype "passive"))
    )
    (net (code "111") (name "unconnected-(S1-Pad1)") (class "Default")
      (node (ref "S1") (pin "1") (pinfunction "1_1") (pintype "passive"))
    )
    (net (code "112") (name "unconnected-(U$1-RST-PadJ1_3)") (class "Default")
      (node (ref "U$1") (pin "J1_3") (pinfunction "RST_J1_3") (pintype "input"))
    )
    (net (code "113") (name "unconnected-(U$1-U0RXD{slash}GPIO44-PadJ3_3)") (class "Default")
      (node (ref "U$1") (pin "J3_3") (pinfunction "U0RXD/GPIO44_J3_3") (pintype "bidirectional"))
    )
    (net (code "114") (name "unconnected-(U$1-U0TXD{slash}GPIO43-PadJ3_2)") (class "Default")
      (node (ref "U$1") (pin "J3_2") (pinfunction "U0TXD/GPIO43_J3_2") (pintype "bidirectional"))
    )
    (net (code "115") (name "unconnected-(U$2-1-Pad5)") (class "Default")
      (node (ref "U$2") (pin "5") (pinfunction "1_5") (pintype "passive"))
    )
    (net (code "116") (name "unconnected-(U$2-2-Pad6)") (class "Default")
      (node (ref "U$2") (pin "6") (pinfunction "2_6") (pintype "passive"))
    )
    (net (code "117") (name "unconnected-(U$2-3-Pad7)") (class "Default")
      (node (ref "U$2") (pin "7") (pinfunction "3_7") (pintype "passive"))
    )
    (net (code "118") (name "unconnected-(U$2-4-Pad8)") (class "Default")
      (node (ref "U$2") (pin "8") (pinfunction "4_8") (pintype "passive"))
    )
    (net (code "119") (name "unconnected-(U$2-5-Pad9)") (class "Default")
      (node (ref "U$2") (pin "9") (pinfunction "5_9") (pintype "passive"))
    )
    (net (code "120") (name "unconnected-(U$2-8-Pad2)") (class "Default")
      (node (ref "U$2") (pin "2") (pinfunction "8_2") (pintype "passive"))
    )
    (net (code "121") (name "unconnected-(U$2-9-Pad3)") (class "Default")
      (node (ref "U$2") (pin "3") (pinfunction "9_3") (pintype "passive"))
    )
    (net (code "122") (name "unconnected-(U$7-AN_IN1+-Pad24)") (class "Default")
      (node (ref "U$7") (pin "24") (pinfunction "AN_IN1+_24") (pintype "bidirectional"))
    )
    (net (code "123") (name "unconnected-(U$7-AN_IN1--Pad23)") (class "Default")
      (node (ref "U$7") (pin "23") (pinfunction "AN_IN1-_23") (pintype "bidirectional"))
    )
    (net (code "124") (name "unconnected-(U$7-AN_IN2+-Pad22)") (class "Default")
      (node (ref "U$7") (pin "22") (pinfunction "AN_IN2+_22") (pintype "bidirectional"))
    )
    (net (code "125") (name "unconnected-(U$7-AN_IN2--Pad21)") (class "Default")
      (node (ref "U$7") (pin "21") (pinfunction "AN_IN2-_21") (pintype "bidirectional"))
    )
    (net (code "126") (name "unconnected-(U$7-DIG_IN2-Pad16)") (class "Default")
      (node (ref "U$7") (pin "16") (pinfunction "DIG_IN2_16") (pintype "bidirectional"))
    )
    (net (code "127") (name "unconnected-(U$8-1-PadA1)") (class "Default")
      (node (ref "U$8") (pin "A1") (pinfunction "1_A1") (pintype "bidirectional"))
    )
    (net (code "128") (name "unconnected-(U$8-4-PadA4)") (class "Default")
      (node (ref "U$8") (pin "A4") (pinfunction "4_A4") (pintype "bidirectional"))
    )
    (net (code "129") (name "unconnected-(U$8-9-PadA9)") (class "Default")
      (node (ref "U$8") (pin "A9") (pinfunction "9_A9") (pintype "bidirectional"))
    )
    (net (code "130") (name "unconnected-(U$8-10-PadA10)") (class "Default")
      (node (ref "U$8") (pin "A10") (pinfunction "10_A10") (pintype "bidirectional"))
    )
    (net (code "131") (name "unconnected-(U$9-AN_IN1+-Pad24)") (class "Default")
      (node (ref "U$9") (pin "24") (pinfunction "AN_IN1+_24") (pintype "bidirectional"))
    )
    (net (code "132") (name "unconnected-(U$9-AN_IN1--Pad23)") (class "Default")
      (node (ref "U$9") (pin "23") (pinfunction "AN_IN1-_23") (pintype "bidirectional"))
    )
    (net (code "133") (name "unconnected-(U$9-AN_IN2+-Pad22)") (class "Default")
      (node (ref "U$9") (pin "22") (pinfunction "AN_IN2+_22") (pintype "bidirectional"))
    )
    (net (code "134") (name "unconnected-(U$9-AN_IN2--Pad21)") (class "Default")
      (node (ref "U$9") (pin "21") (pinfunction "AN_IN2-_21") (pintype "bidirectional"))
    )
    (net (code "135") (name "unconnected-(U$9-DIG_IN2-Pad16)") (class "Default")
      (node (ref "U$9") (pin "16") (pinfunction "DIG_IN2_16") (pintype "bidirectional"))
    )
    (net (code "136") (name "unconnected-(U$10-6-PadB6)") (class "Default")
      (node (ref "U$10") (pin "B6") (pinfunction "6_B6") (pintype "bidirectional"))
    )
    (net (code "137") (name "unconnected-(U$11-1-PadA1)") (class "Default")
      (node (ref "U$11") (pin "A1") (pinfunction "1_A1") (pintype "bidirectional"))
    )
    (net (code "138") (name "unconnected-(U$11-4-PadA4)") (class "Default")
      (node (ref "U$11") (pin "A4") (pinfunction "4_A4") (pintype "bidirectional"))
    )
    (net (code "139") (name "unconnected-(U$11-9-PadA9)") (class "Default")
      (node (ref "U$11") (pin "A9") (pinfunction "9_A9") (pintype "bidirectional"))
    )
    (net (code "140") (name "unconnected-(U$11-10-PadA10)") (class "Default")
      (node (ref "U$11") (pin "A10") (pinfunction "10_A10") (pintype "bidirectional"))
    )
    (net (code "141") (name "unconnected-(U$12-6-PadB6)") (class "Default")
      (node (ref "U$12") (pin "B6") (pinfunction "6_B6") (pintype "bidirectional"))
    )
    (net (code "142") (name "unconnected-(U$13-4-PadC4)") (class "Default")
      (node (ref "U$13") (pin "C4") (pinfunction "4_C4") (pintype "bidirectional"))
    )
    (net (code "143") (name "unconnected-(U$14-4-PadC4)") (class "Default")
      (node (ref "U$14") (pin "C4") (pinfunction "4_C4") (pintype "bidirectional"))
    )
  )
)
